# SupplyBoxTest_v2.net
KiCad netlist of a schematic drawn in Altium Designer
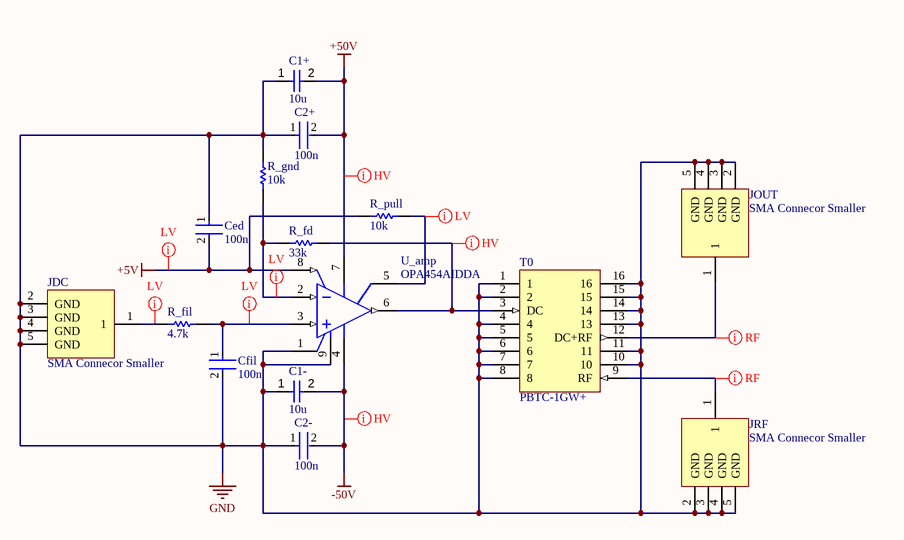
[diagram p0: SupplyBoxTest_v2.SchDoc]

(export (version "E")
  (design (tool "Eeschema 10.0.6"))
  (components
    (comp (ref "C1+")
      (value "10u")
      (footprint "RAHV1100M1UCC8002E-Footprint-1")
      (libsource (lib "Li-Ren Liu") (part "CAP-NP-2"))
    )
    (comp (ref "C1-")
      (value "10u")
      (footprint "RAHV1100M1UCC8002E-Footprint-1")
      (libsource (lib "Li-Ren Liu") (part "CAP-NP-2"))
    )
    (comp (ref "C2+")
      (value "100n")
      (footprint "FP-CC0805-0_85-MFG")
      (description "CAP CER 0.1UF 25V X7R 0805")
      (fields (field (name "MANUFACTURER PART NUMBER") "CC0805KRX7R8BB104") (field (name "TOLERANCE") "0.1"))
      (libsource (lib "Altium Content Vault") (part "11868f565c42a9108669ba33697ecf6"))
    )
    (comp (ref "C2-")
      (value "100n")
      (footprint "FP-CC0805-0_85-MFG")
      (description "CAP CER 0.1UF 25V X7R 0805")
      (fields (field (name "MANUFACTURER PART NUMBER") "CC0805KRX7R8BB104") (field (name "TOLERANCE") "0.1"))
      (libsource (lib "Altium Content Vault") (part "11868f565c42a9108669ba33697ecf6"))
    )
    (comp (ref "Ced")
      (value "100n")
      (footprint "FP-CC0805-0_85-MFG")
      (description "CAP CER 0.1UF 25V X7R 0805")
      (fields (field (name "MANUFACTURER PART NUMBER") "CC0805KRX7R8BB104") (field (name "TOLERANCE") "0.1"))
      (libsource (lib "Altium Content Vault") (part "11868f565c42a9108669ba33697ecf6"))
    )
    (comp (ref "Cfil")
      (value "100n")
      (footprint "FP-CC0805-0_85-MFG")
      (description "CAP CER 0.1UF 25V X7R 0805")
      (fields (field (name "MANUFACTURER PART NUMBER") "CC0805KRX7R8BB104") (field (name "TOLERANCE") "0.1"))
      (libsource (lib "Altium Content Vault") (part "11868f565c42a9108669ba33697ecf6"))
    )
    (comp (ref "JDC")
      (value "SMA Connecor Smaller")
      (footprint "SMA_Smaller")
      (description "Smaller SMA connector we bought from amazon.com")
      (libsource (lib "") (part "SMA CONN_2"))
    )
    (comp (ref "JOUT")
      (value "SMA Connecor Smaller")
      (footprint "SMA_Smaller")
      (description "Smaller SMA connector we bought from amazon.com")
      (libsource (lib "Zijue Luo") (part "SMA CONN"))
    )
    (comp (ref "JRF")
      (value "SMA Connecor Smaller")
      (footprint "SMA_Smaller")
      (description "Smaller SMA connector we bought from amazon.com")
      (libsource (lib "") (part "SMA CONN_1"))
    )
    (comp (ref "R_fd")
      (value "33k")
      (footprint "RESC2013X60X35ML10T20")
      (description "Chip Resistor, 3.3 KOhm, +/- 1%, 0.125 W, -55 to 155 degC, 0805 (2012 Metric), RoHS, Tape and Reel")
      (fields (field (name "TOLERANCE") "1%") (field (name "MANUFACTURER") "Yageo"))
      (libsource (lib "Altium Content Vault") (part "RES-2"))
    )
    (comp (ref "R_fil")
      (value "4.7k")
      (footprint "RESC2013X60X35NL10T20")
      (description "Chip Resistor, 47 KOhm, +/- 1%, 0.125 W, -55 to 155 degC, 0805 (2012 Metric), RoHS, Tape and Reel")
      (fields (field (name "MANUFACTURER") "Yageo"))
      (libsource (lib "Altium Content Vault") (part "RES-2"))
    )
    (comp (ref "R_gnd")
      (value "10k")
      (footprint "RESC2013X60X35ML10T20")
      (description "Chip Resistor, 1 KOhm, +/- 1%, 125 mW, -55 to 155 degC, 0805 (2012 Metric), RoHS, Tape and Reel")
      (fields (field (name "TOLERANCE") "1%") (field (name "MANUFACTURER") "Yageo"))
      (libsource (lib "Altium Content Vault") (part "RES-2"))
    )
    (comp (ref "R_pull")
      (value "10k")
      (footprint "RESC2013X60X35ML10T20")
      (description "Chip Resistor, 1 KOhm, +/- 1%, 125 mW, -55 to 155 degC, 0805 (2012 Metric), RoHS, Tape and Reel")
      (fields (field (name "TOLERANCE") "1%") (field (name "MANUFACTURER") "Yageo"))
      (libsource (lib "Altium Content Vault") (part "RES-2"))
    )
    (comp (ref "T0")
      (value "PBTC-1GW+")
      (footprint "PBTC-1GW+")
      (description "Mini-Circuit Bias-Tee, version 2")
      (libsource (lib "Zijue Luo") (part "PBTC-1GW+"))
    )
    (comp (ref "U_amp")
      (value "OPA454AIDDA")
      (footprint "DDA0008C_L")
      (fields (field (name "MANUFACTURER") "Texas Instruments"))
      (libsource (lib "Altium Content Vault") (part "TI-OPA454-DDA8"))
    )
  )
  (nets
    (net (code "1") (name "+5V") (class "Default")
      (node (ref "Ced") (pin "2") (pinfunction "2_2") (pintype "passive"))
      (node (ref "R_pull") (pin "1") (pinfunction "1_1") (pintype "passive"))
      (node (ref "U_amp") (pin "8") (pinfunction "E/D_8") (pintype "input"))
    )
    (net (code "2") (name "+50V") (class "Default")
      (node (ref "C1+") (pin "2") (pinfunction "2_2") (pintype "passive"))
      (node (ref "C2+") (pin "2") (pinfunction "2_2") (pintype "passive"))
      (node (ref "U_amp") (pin "7") (pinfunction "V+_7") (pintype "power_in"))
    )
    (net (code "3") (name "-50V") (class "Default")
      (node (ref "C1-") (pin "2") (pinfunction "2_2") (pintype "passive"))
      (node (ref "C2-") (pin "2") (pinfunction "2_2") (pintype "passive"))
      (node (ref "U_amp") (pin "4") (pinfunction "V-_4") (pintype "power_in"))
    )
    (net (code "4") (name "GND") (class "Default")
      (node (ref "C1+") (pin "1") (pinfunction "1_1") (pintype "passive"))
      (node (ref "C1-") (pin "1") (pinfunction "1_1") (pintype "passive"))
      (node (ref "C2+") (pin "1") (pinfunction "1_1") (pintype "passive"))
      (node (ref "C2-") (pin "1") (pinfunction "1_1") (pintype "passive"))
      (node (ref "Ced") (pin "1") (pinfunction "1_1") (pintype "passive"))
      (node (ref "Cfil") (pin "2") (pinfunction "2_2") (pintype "passive"))
      (node (ref "JDC") (pin "2") (pinfunction "GND_2") (pintype "passive"))
      (node (ref "JDC") (pin "3") (pinfunction "GND_3") (pintype "passive"))
      (node (ref "JDC") (pin "4") (pinfunction "GND_4") (pintype "passive"))
      (node (ref "JDC") (pin "5") (pinfunction "GND_5") (pintype "passive"))
      (node (ref "JOUT") (pin "2") (pinfunction "GND_2") (pintype "passive"))
      (node (ref "JOUT") (pin "3") (pinfunction "GND_3") (pintype "passive"))
      (node (ref "JOUT") (pin "4") (pinfunction "GND_4") (pintype "passive"))
      (node (ref "JOUT") (pin "5") (pinfunction "GND_5") (pintype "passive"))
      (node (ref "JRF") (pin "2") (pinfunction "GND_2") (pintype "passive"))
      (node (ref "JRF") (pin "3") (pinfunction "GND_3") (pintype "passive"))
      (node (ref "JRF") (pin "4") (pinfunction "GND_4") (pintype "passive"))
      (node (ref "JRF") (pin "5") (pinfunction "GND_5") (pintype "passive"))
      (node (ref "R_gnd") (pin "1") (pinfunction "1_1") (pintype "passive"))
      (node (ref "T0") (pin "1") (pinfunction "1_1") (pintype "passive"))
      (node (ref "T0") (pin "10") (pinfunction "10_10") (pintype "passive"))
      (node (ref "T0") (pin "11") (pinfunction "11_11") (pintype "passive"))
      (node (ref "T0") (pin "13") (pinfunction "13_13") (pintype "passive"))
      (node (ref "T0") (pin "14") (pinfunction "14_14") (pintype "passive"))
      (node (ref "T0") (pin "15") (pinfunction "15_15") (pintype "passive"))
      (node (ref "T0") (pin "16") (pinfunction "16_16") (pintype "passive"))
      (node (ref "T0") (pin "2") (pinfunction "2_2") (pintype "passive"))
      (node (ref "T0") (pin "4") (pinfunction "4_4") (pintype "passive"))
      (node (ref "T0") (pin "5") (pinfunction "5_5") (pintype "passive"))
      (node (ref "T0") (pin "6") (pinfunction "6_6") (pintype "passive"))
      (node (ref "T0") (pin "7") (pinfunction "7_7") (pintype "passive"))
      (node (ref "T0") (pin "8") (pinfunction "8_8") (pintype "passive"))
      (node (ref "U_amp") (pin "1") (pinfunction "E/D_COM_1") (pintype "power_in"))
      (node (ref "U_amp") (pin "9") (pinfunction "EP_9") (pintype "power_in"))
    )
    (net (code "5") (name "Net-(JDC-Pad1)") (class "Default")
      (node (ref "JDC") (pin "1") (pinfunction "1_1") (pintype "passive"))
      (node (ref "R_fil") (pin "1") (pinfunction "1_1") (pintype "passive"))
    )
    (net (code "6") (name "Net-(T0-DC)") (class "Default")
      (node (ref "R_fd") (pin "2") (pinfunction "2_2") (pintype "passive"))
      (node (ref "T0") (pin "3") (pinfunction "DC_3") (pintype "input"))
      (node (ref "U_amp") (pin "6") (pinfunction "OUT_6") (pintype "output"))
    )
    (net (code "7") (name "Net-(T0-DC+RF)") (class "Default")
      (node (ref "JOUT") (pin "1") (pinfunction "1_1") (pintype "passive"))
      (node (ref "T0") (pin "12") (pinfunction "DC+RF_12") (pintype "output"))
    )
    (net (code "8") (name "Net-(T0-RF)") (class "Default")
      (node (ref "JRF") (pin "1") (pinfunction "1_1") (pintype "passive"))
      (node (ref "T0") (pin "9") (pinfunction "RF_9") (pintype "input"))
    )
    (net (code "9") (name "Net-(U_amp-IN+)") (class "Default")
      (node (ref "Cfil") (pin "1") (pinfunction "1_1") (pintype "passive"))
      (node (ref "R_fil") (pin "2") (pinfunction "2_2") (pintype "passive"))
      (node (ref "U_amp") (pin "3") (pinfunction "IN+_3") (pintype "input"))
    )
    (net (code "10") (name "Net-(U_amp-IN-)") (class "Default")
      (node (ref "R_fd") (pin "1") (pinfunction "1_1") (pintype "passive"))
      (node (ref "R_gnd") (pin "2") (pinfunction "2_2") (pintype "passive"))
      (node (ref "U_amp") (pin "2") (pinfunction "IN-_2") (pintype "input"))
    )
    (net (code "11") (name "Net-(U_amp-STATUS_FLAG)") (class "Default")
      (node (ref "R_pull") (pin "2") (pinfunction "2_2") (pintype "passive"))
      (node (ref "U_amp") (pin "5") (pinfunction "STATUS_FLAG_5") (pintype "open_collector"))
    )
  )
)
